# WIK_pl_DC.net
KiCad netlist of a schematic drawn in EAGLE
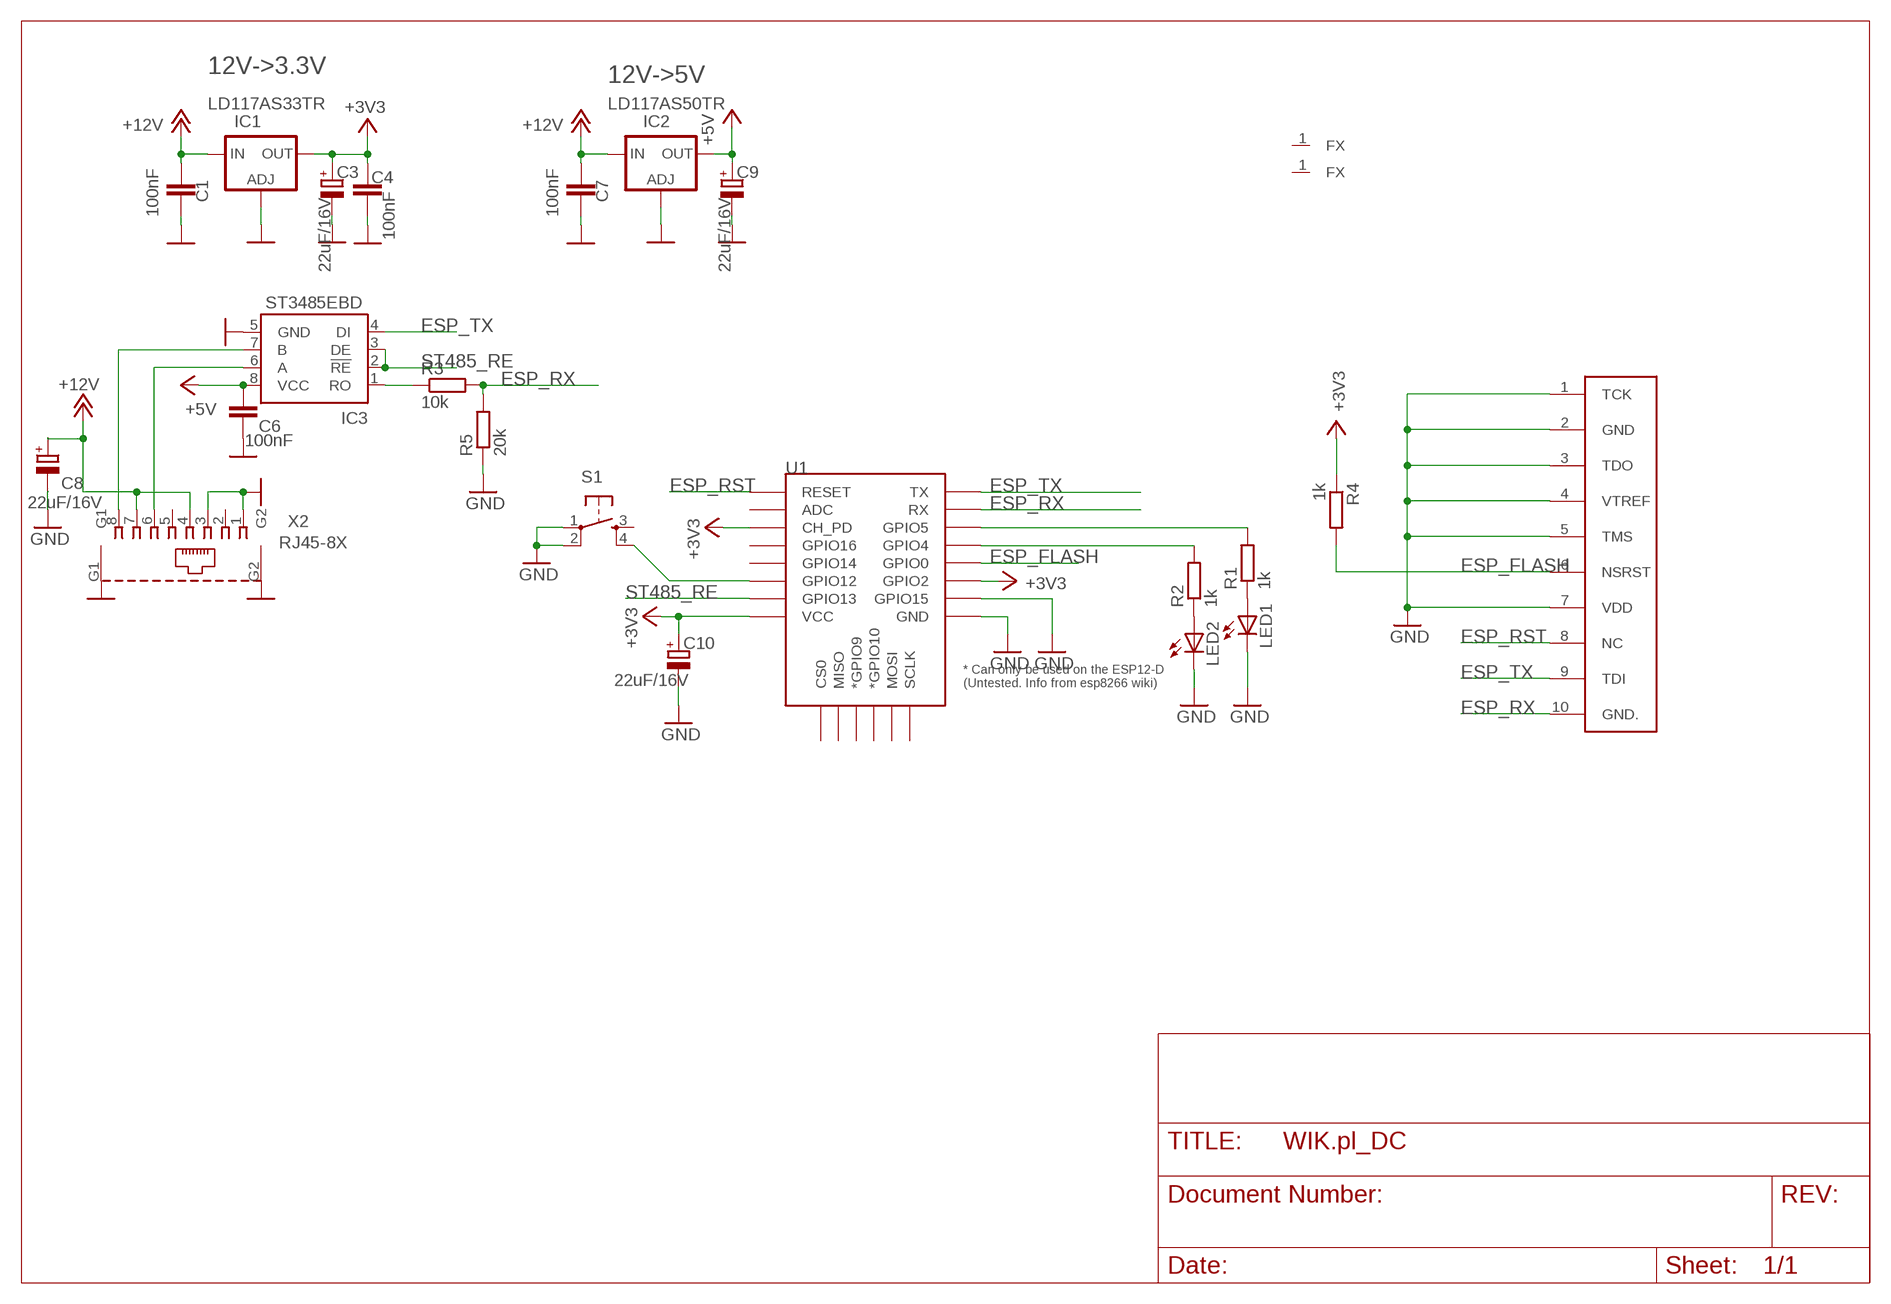
[diagram p0: schematic, sheet 1]

(export (version "E")
  (design (tool "Eeschema 10.0.6"))
  (components
    (comp (ref "C1")
      (value "100nF")
      (footprint "eagle-import:C0805")
      (libsource (lib "eagle-import") (part "C-EUC0805"))
    )
    (comp (ref "C3")
      (value "22uF/16V")
      (footprint "eagle-import:SMC_B")
      (libsource (lib "eagle-import") (part "CPOL-EUSMCB"))
    )
    (comp (ref "C4")
      (value "100nF")
      (footprint "eagle-import:C0805")
      (libsource (lib "eagle-import") (part "C-EUC0805"))
    )
    (comp (ref "C6")
      (value "100nF")
      (footprint "eagle-import:C0805")
      (libsource (lib "eagle-import") (part "C-EUC0805"))
    )
    (comp (ref "C7")
      (value "100nF")
      (footprint "eagle-import:C0805")
      (libsource (lib "eagle-import") (part "C-EUC0805"))
    )
    (comp (ref "C8")
      (value "22uF/16V")
      (footprint "eagle-import:SMC_B")
      (libsource (lib "eagle-import") (part "CPOL-EUSMCB"))
    )
    (comp (ref "C9")
      (value "22uF/16V")
      (footprint "eagle-import:SMC_B")
      (libsource (lib "eagle-import") (part "CPOL-EUSMCB"))
    )
    (comp (ref "C10")
      (value "22uF/16V")
      (footprint "eagle-import:SMC_B")
      (libsource (lib "eagle-import") (part "CPOL-EUSMCB"))
    )
    (comp (ref "IC1")
      (value "LD117AS33TR")
      (footprint "eagle-import:SOT223")
      (libsource (lib "eagle-import") (part "LD117A?S33TR"))
    )
    (comp (ref "IC2")
      (value "LD117AS50TR")
      (footprint "eagle-import:SOT223")
      (libsource (lib "eagle-import") (part "LD117A?S50TR"))
    )
    (comp (ref "IC3")
      (value "ST3485EBD")
      (footprint "eagle-import:SOIC8")
      (libsource (lib "eagle-import") (part "LTC485S"))
    )
    (comp (ref "LED1")
      (value "LED1206")
      (footprint "eagle-import:LED-1206")
      (libsource (lib "eagle-import") (part "LED1206"))
    )
    (comp (ref "LED2")
      (value "LED1206")
      (footprint "eagle-import:LED-1206")
      (libsource (lib "eagle-import") (part "LED1206"))
    )
    (comp (ref "R1")
      (value "1k")
      (footprint "eagle-import:R0805")
      (libsource (lib "eagle-import") (part "R-EU_R0805"))
    )
    (comp (ref "R2")
      (value "1k")
      (footprint "eagle-import:R0805")
      (libsource (lib "eagle-import") (part "R-EU_R0805"))
    )
    (comp (ref "R3")
      (value "10k")
      (footprint "eagle-import:R0805")
      (libsource (lib "eagle-import") (part "R-EU_R0805"))
    )
    (comp (ref "R4")
      (value "1k")
      (footprint "eagle-import:R0805")
      (libsource (lib "eagle-import") (part "R-EU_R0805"))
    )
    (comp (ref "R5")
      (value "20k")
      (footprint "eagle-import:R0805")
      (libsource (lib "eagle-import") (part "R-EU_R0805"))
    )
    (comp (ref "S1")
      (value "TAC_SWITCHPTH")
      (footprint "eagle-import:TACTILE-PTH")
      (libsource (lib "eagle-import") (part "TAC_SWITCHPTH"))
    )
    (comp (ref "U$1")
      (value "FIDUCIAL")
      (footprint "eagle-import:FIDUCIAL")
      (libsource (lib "eagle-import") (part "FIDUCIAL"))
    )
    (comp (ref "U$2")
      (value "FIDUCIAL")
      (footprint "eagle-import:FIDUCIAL")
      (libsource (lib "eagle-import") (part "FIDUCIAL"))
    )
    (comp (ref "U$3")
      (value "TC2050-IDC-NL")
      (footprint "eagle-import:TC2050-IDC-NL")
      (libsource (lib "eagle-import") (part "TC2050-IDC-NL"))
    )
    (comp (ref "U1")
      (value "ESP12ESMD")
      (footprint "eagle-import:ESP12E-SMD")
      (libsource (lib "eagle-import") (part "ESP12ESMD"))
    )
    (comp (ref "X2")
      (value "RJ45-8X")
      (footprint "eagle-import:RJ45-NO-SHIELD")
      (libsource (lib "eagle-import") (part "RJ45-8X"))
    )
  )
  (nets
    (net (code "1") (name "+3V3") (class "Default")
      (node (ref "C10") (pin "+") (pinfunction "+_+") (pintype "passive"))
      (node (ref "C3") (pin "+") (pinfunction "+_+") (pintype "passive"))
      (node (ref "C4") (pin "1") (pinfunction "1_1") (pintype "passive"))
      (node (ref "IC1") (pin "4") (pinfunction "OUT_4") (pintype "passive"))
      (node (ref "R4") (pin "1") (pinfunction "1_1") (pintype "passive"))
      (node (ref "U1") (pin "CH_PD") (pinfunction "CH_PD_CH_PD") (pintype "bidirectional"))
      (node (ref "U1") (pin "GPIO2") (pinfunction "GPIO2_GPIO2") (pintype "bidirectional"))
      (node (ref "U1") (pin "VCC") (pinfunction "VCC_VCC") (pintype "bidirectional"))
    )
    (net (code "2") (name "+5V") (class "Default")
      (node (ref "C6") (pin "2") (pinfunction "2_2") (pintype "passive"))
      (node (ref "C9") (pin "+") (pinfunction "+_+") (pintype "passive"))
      (node (ref "IC2") (pin "4") (pinfunction "OUT_4") (pintype "passive"))
      (node (ref "IC3") (pin "8") (pinfunction "VCC_8") (pintype "input"))
    )
    (net (code "3") (name "+12V") (class "Default")
      (node (ref "C1") (pin "1") (pinfunction "1_1") (pintype "passive"))
      (node (ref "C7") (pin "1") (pinfunction "1_1") (pintype "passive"))
      (node (ref "C8") (pin "+") (pinfunction "+_+") (pintype "passive"))
      (node (ref "IC1") (pin "3") (pinfunction "IN_3") (pintype "input"))
      (node (ref "IC2") (pin "3") (pinfunction "IN_3") (pintype "input"))
      (node (ref "X2") (pin "4") (pinfunction "4_4") (pintype "passive"))
      (node (ref "X2") (pin "7") (pinfunction "7_7") (pintype "passive"))
    )
    (net (code "4") (name "/ESP_FLASH") (class "Default")
      (node (ref "R4") (pin "2") (pinfunction "2_2") (pintype "passive"))
      (node (ref "U$3") (pin "6") (pinfunction "NSRST_6") (pintype "bidirectional"))
      (node (ref "U1") (pin "GPIO0") (pinfunction "GPIO0_GPIO0") (pintype "bidirectional"))
    )
    (net (code "5") (name "/ESP_RST") (class "Default")
      (node (ref "U$3") (pin "8") (pinfunction "NC_8") (pintype "bidirectional"))
      (node (ref "U1") (pin "RESET") (pinfunction "RESET_RESET") (pintype "bidirectional"))
    )
    (net (code "6") (name "/ESP_RX") (class "Default")
      (node (ref "R3") (pin "2") (pinfunction "2_2") (pintype "passive"))
      (node (ref "R5") (pin "2") (pinfunction "2_2") (pintype "passive"))
      (node (ref "U$3") (pin "10") (pinfunction "GND._10") (pintype "bidirectional"))
      (node (ref "U1") (pin "RXD0") (pinfunction "RX_RXD0") (pintype "bidirectional"))
    )
    (net (code "7") (name "/ESP_TX") (class "Default")
      (node (ref "IC3") (pin "4") (pinfunction "DI_4") (pintype "input"))
      (node (ref "U$3") (pin "9") (pinfunction "TDI_9") (pintype "bidirectional"))
      (node (ref "U1") (pin "TXD0") (pinfunction "TX_TXD0") (pintype "bidirectional"))
    )
    (net (code "8") (name "/ST485_RE") (class "Default")
      (node (ref "IC3") (pin "2") (pinfunction "~{RE}_2") (pintype "input"))
      (node (ref "IC3") (pin "3") (pinfunction "DE_3") (pintype "input"))
      (node (ref "U1") (pin "GPIO13") (pinfunction "GPIO13_GPIO13") (pintype "bidirectional"))
    )
    (net (code "9") (name "GND") (class "Default")
      (node (ref "C1") (pin "2") (pinfunction "2_2") (pintype "passive"))
      (node (ref "C10") (pin "-") (pinfunction "-_-") (pintype "passive"))
      (node (ref "C3") (pin "-") (pinfunction "-_-") (pintype "passive"))
      (node (ref "C4") (pin "2") (pinfunction "2_2") (pintype "passive"))
      (node (ref "C6") (pin "1") (pinfunction "1_1") (pintype "passive"))
      (node (ref "C7") (pin "2") (pinfunction "2_2") (pintype "passive"))
      (node (ref "C8") (pin "-") (pinfunction "-_-") (pintype "passive"))
      (node (ref "C9") (pin "-") (pinfunction "-_-") (pintype "passive"))
      (node (ref "IC1") (pin "1") (pinfunction "ADJ_1") (pintype "input"))
      (node (ref "IC2") (pin "1") (pinfunction "ADJ_1") (pintype "input"))
      (node (ref "IC3") (pin "5") (pinfunction "GND_5") (pintype "input"))
      (node (ref "LED1") (pin "C") (pinfunction "C_C") (pintype "passive"))
      (node (ref "LED2") (pin "C") (pinfunction "C_C") (pintype "passive"))
      (node (ref "R5") (pin "1") (pinfunction "1_1") (pintype "passive"))
      (node (ref "S1") (pin "1") (pinfunction "1_1") (pintype "passive"))
      (node (ref "S1") (pin "2") (pinfunction "2_2") (pintype "passive"))
      (node (ref "U$3") (pin "1") (pinfunction "TCK_1") (pintype "bidirectional"))
      (node (ref "U$3") (pin "2") (pinfunction "GND_2") (pintype "bidirectional"))
      (node (ref "U$3") (pin "3") (pinfunction "TDO_3") (pintype "bidirectional"))
      (node (ref "U$3") (pin "4") (pinfunction "VTREF_4") (pintype "bidirectional"))
      (node (ref "U$3") (pin "5") (pinfunction "TMS_5") (pintype "bidirectional"))
      (node (ref "U$3") (pin "7") (pinfunction "VDD_7") (pintype "bidirectional"))
      (node (ref "U1") (pin "GND") (pinfunction "GND_GND") (pintype "bidirectional"))
      (node (ref "U1") (pin "GPIO15") (pinfunction "GPIO15_GPIO15") (pintype "bidirectional"))
      (node (ref "X2") (pin "1") (pinfunction "1_1") (pintype "passive"))
      (node (ref "X2") (pin "3") (pinfunction "3_3") (pintype "passive"))
      (node (ref "X2") (pin "G1") (pinfunction "G1_G1") (pintype "power_in"))
      (node (ref "X2") (pin "G2") (pinfunction "G2_G2") (pintype "power_in"))
    )
    (net (code "10") (name "Net-(IC3-A)") (class "Default")
      (node (ref "IC3") (pin "6") (pinfunction "A_6") (pintype "bidirectional"))
      (node (ref "X2") (pin "6") (pinfunction "6_6") (pintype "passive"))
    )
    (net (code "11") (name "Net-(IC3-B)") (class "Default")
      (node (ref "IC3") (pin "7") (pinfunction "B_7") (pintype "bidirectional"))
      (node (ref "X2") (pin "8") (pinfunction "8_8") (pintype "passive"))
    )
    (net (code "12") (name "Net-(IC3-RO)") (class "Default")
      (node (ref "IC3") (pin "1") (pinfunction "RO_1") (pintype "output"))
      (node (ref "R3") (pin "1") (pinfunction "1_1") (pintype "passive"))
    )
    (net (code "13") (name "Net-(LED1-PadA)") (class "Default")
      (node (ref "LED1") (pin "A") (pinfunction "A_A") (pintype "passive"))
      (node (ref "R1") (pin "1") (pinfunction "1_1") (pintype "passive"))
    )
    (net (code "14") (name "Net-(LED2-PadA)") (class "Default")
      (node (ref "LED2") (pin "A") (pinfunction "A_A") (pintype "passive"))
      (node (ref "R2") (pin "1") (pinfunction "1_1") (pintype "passive"))
    )
    (net (code "15") (name "Net-(R1-Pad2)") (class "Default")
      (node (ref "R1") (pin "2") (pinfunction "2_2") (pintype "passive"))
      (node (ref "U1") (pin "GPIO5") (pinfunction "GPIO5_GPIO5") (pintype "bidirectional"))
    )
    (net (code "16") (name "Net-(R2-Pad2)") (class "Default")
      (node (ref "R2") (pin "2") (pinfunction "2_2") (pintype "passive"))
      (node (ref "U1") (pin "GPIO4") (pinfunction "GPIO4_GPIO4") (pintype "bidirectional"))
    )
    (net (code "17") (name "Net-(S1-Pad4)") (class "Default")
      (node (ref "S1") (pin "4") (pinfunction "4_4") (pintype "passive"))
      (node (ref "U1") (pin "GPIO12") (pinfunction "GPIO12_GPIO12") (pintype "bidirectional"))
    )
    (net (code "18") (name "unconnected-(S1-Pad3)") (class "Default")
      (node (ref "S1") (pin "3") (pinfunction "3_3") (pintype "passive"))
    )
    (net (code "19") (name "unconnected-(U$1-FX-Pad1)") (class "Default")
      (node (ref "U$1") (pin "1") (pinfunction "FX_1") (pintype "bidirectional"))
    )
    (net (code "20") (name "unconnected-(U$2-FX-Pad1)") (class "Default")
      (node (ref "U$2") (pin "1") (pinfunction "FX_1") (pintype "bidirectional"))
    )
    (net (code "21") (name "unconnected-(U1-*GPIO9-PadGPIO9)") (class "Default")
      (node (ref "U1") (pin "GPIO9") (pinfunction "*GPIO9_GPIO9") (pintype "bidirectional"))
    )
    (net (code "22") (name "unconnected-(U1-*GPIO10-PadGPIO10)") (class "Default")
      (node (ref "U1") (pin "GPIO10") (pinfunction "*GPIO10_GPIO10") (pintype "bidirectional"))
    )
    (net (code "23") (name "unconnected-(U1-PadADC)") (class "Default")
      (node (ref "U1") (pin "ADC") (pinfunction "ADC_ADC") (pintype "bidirectional"))
    )
    (net (code "24") (name "unconnected-(U1-PadCS0)") (class "Default")
      (node (ref "U1") (pin "CS0") (pinfunction "CS0_CS0") (pintype "bidirectional"))
    )
    (net (code "25") (name "unconnected-(U1-PadGPIO14)") (class "Default")
      (node (ref "U1") (pin "GPIO14") (pinfunction "GPIO14_GPIO14") (pintype "bidirectional"))
    )
    (net (code "26") (name "unconnected-(U1-PadGPIO16)") (class "Default")
      (node (ref "U1") (pin "GPIO16") (pinfunction "GPIO16_GPIO16") (pintype "bidirectional"))
    )
    (net (code "27") (name "unconnected-(U1-PadMISO)") (class "Default")
      (node (ref "U1") (pin "MISO") (pinfunction "MISO_MISO") (pintype "bidirectional"))
    )
    (net (code "28") (name "unconnected-(U1-PadMOSI)") (class "Default")
      (node (ref "U1") (pin "MOSI") (pinfunction "MOSI_MOSI") (pintype "bidirectional"))
    )
    (net (code "29") (name "unconnected-(U1-PadSCLK)") (class "Default")
      (node (ref "U1") (pin "SCLK") (pinfunction "SCLK_SCLK") (pintype "bidirectional"))
    )
    (net (code "30") (name "unconnected-(X2-Pad2)") (class "Default")
      (node (ref "X2") (pin "2") (pinfunction "2_2") (pintype "passive"))
    )
    (net (code "31") (name "unconnected-(X2-Pad5)") (class "Default")
      (node (ref "X2") (pin "5") (pinfunction "5_5") (pintype "passive"))
    )
  )
)
